# amplifier.net
KiCad netlist of a schematic drawn in EAGLE
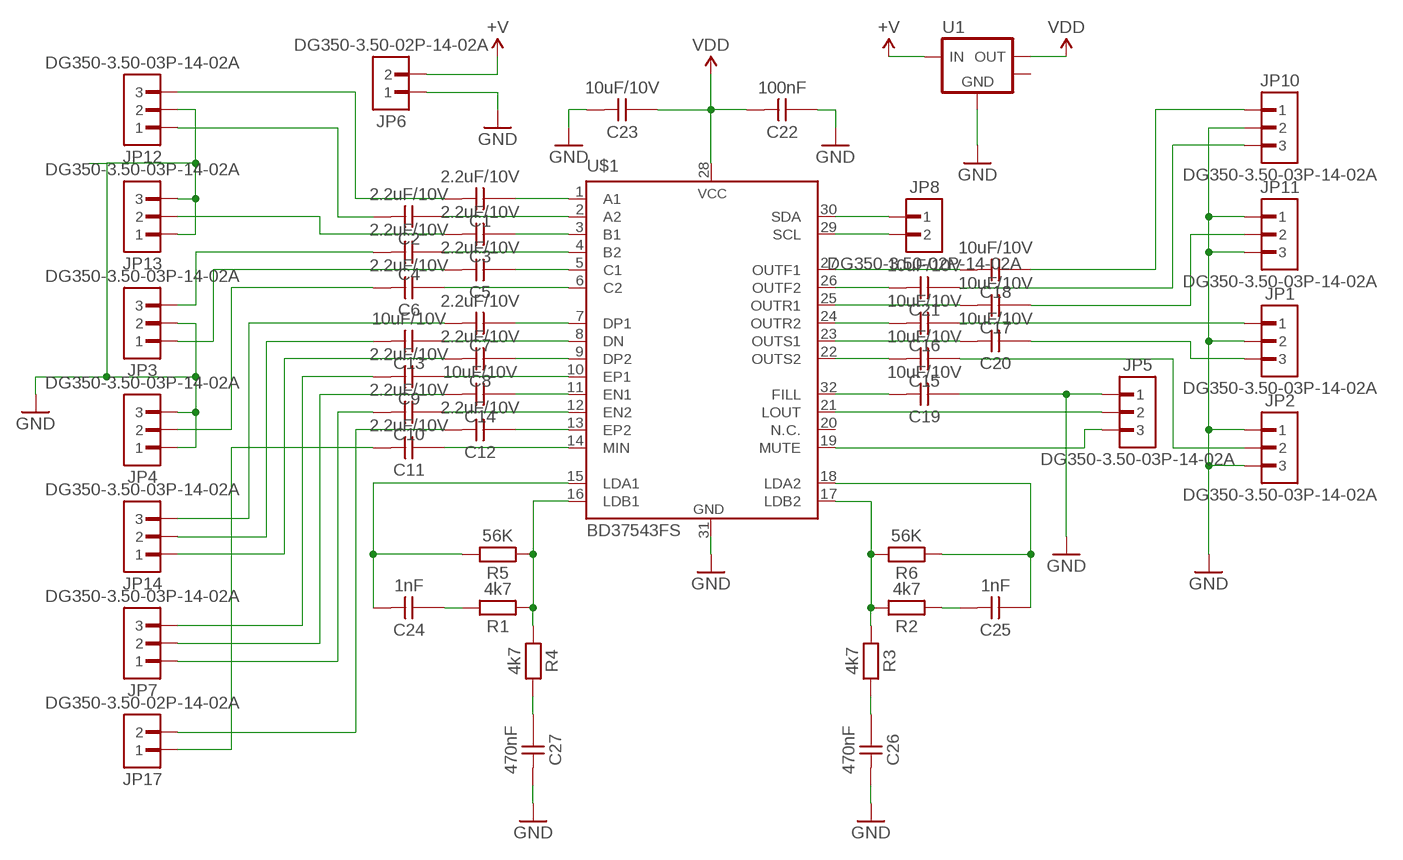
[diagram p0: schematic, sheet 1]

(export (version "E")
  (design (tool "Eeschema 10.0.6"))
  (components
    (comp (ref "C1")
      (value "2.2uF/10V")
      (footprint "eagle-import:CAPACITOR-0805_R")
      (libsource (lib "eagle-import") (part "C-0805-2.2UF-10V"))
    )
    (comp (ref "C2")
      (value "2.2uF/10V")
      (footprint "eagle-import:CAPACITOR-0805_R")
      (libsource (lib "eagle-import") (part "C-0805-2.2UF-10V"))
    )
    (comp (ref "C3")
      (value "2.2uF/10V")
      (footprint "eagle-import:CAPACITOR-0805_R")
      (libsource (lib "eagle-import") (part "C-0805-2.2UF-10V"))
    )
    (comp (ref "C4")
      (value "2.2uF/10V")
      (footprint "eagle-import:CAPACITOR-0805_R")
      (libsource (lib "eagle-import") (part "C-0805-2.2UF-10V"))
    )
    (comp (ref "C5")
      (value "2.2uF/10V")
      (footprint "eagle-import:CAPACITOR-0805_R")
      (libsource (lib "eagle-import") (part "C-0805-2.2UF-10V"))
    )
    (comp (ref "C6")
      (value "2.2uF/10V")
      (footprint "eagle-import:CAPACITOR-0805_R")
      (libsource (lib "eagle-import") (part "C-0805-2.2UF-10V"))
    )
    (comp (ref "C7")
      (value "2.2uF/10V")
      (footprint "eagle-import:CAPACITOR-0805_R")
      (libsource (lib "eagle-import") (part "C-0805-2.2UF-10V"))
    )
    (comp (ref "C8")
      (value "2.2uF/10V")
      (footprint "eagle-import:CAPACITOR-0805_R")
      (libsource (lib "eagle-import") (part "C-0805-2.2UF-10V"))
    )
    (comp (ref "C9")
      (value "2.2uF/10V")
      (footprint "eagle-import:CAPACITOR-0805_R")
      (libsource (lib "eagle-import") (part "C-0805-2.2UF-10V"))
    )
    (comp (ref "C10")
      (value "2.2uF/10V")
      (footprint "eagle-import:CAPACITOR-0805_R")
      (libsource (lib "eagle-import") (part "C-0805-2.2UF-10V"))
    )
    (comp (ref "C11")
      (value "2.2uF/10V")
      (footprint "eagle-import:CAPACITOR-0805_R")
      (libsource (lib "eagle-import") (part "C-0805-2.2UF-10V"))
    )
    (comp (ref "C12")
      (value "2.2uF/10V")
      (footprint "eagle-import:CAPACITOR-0805_R")
      (libsource (lib "eagle-import") (part "C-0805-2.2UF-10V"))
    )
    (comp (ref "C13")
      (value "10uF/10V")
      (footprint "eagle-import:CAPACITOR-0805_R")
      (libsource (lib "eagle-import") (part "C-0805-10UF-10V"))
    )
    (comp (ref "C14")
      (value "10uF/10V")
      (footprint "eagle-import:CAPACITOR-0805_R")
      (libsource (lib "eagle-import") (part "C-0805-10UF-10V"))
    )
    (comp (ref "C15")
      (value "10uF/10V")
      (footprint "eagle-import:CAPACITOR-0805_R")
      (libsource (lib "eagle-import") (part "C-0805-10UF-10V"))
    )
    (comp (ref "C16")
      (value "10uF/10V")
      (footprint "eagle-import:CAPACITOR-0805_R")
      (libsource (lib "eagle-import") (part "C-0805-10UF-10V"))
    )
    (comp (ref "C17")
      (value "10uF/10V")
      (footprint "eagle-import:CAPACITOR-0805_R")
      (libsource (lib "eagle-import") (part "C-0805-10UF-10V"))
    )
    (comp (ref "C18")
      (value "10uF/10V")
      (footprint "eagle-import:CAPACITOR-0805_R")
      (libsource (lib "eagle-import") (part "C-0805-10UF-10V"))
    )
    (comp (ref "C19")
      (value "10uF/10V")
      (footprint "eagle-import:CAPACITOR-0805_R")
      (libsource (lib "eagle-import") (part "C-0805-10UF-10V"))
    )
    (comp (ref "C20")
      (value "10uF/10V")
      (footprint "eagle-import:CAPACITOR-0805_R")
      (libsource (lib "eagle-import") (part "C-0805-10UF-10V"))
    )
    (comp (ref "C21")
      (value "10uF/10V")
      (footprint "eagle-import:CAPACITOR-0805_R")
      (libsource (lib "eagle-import") (part "C-0805-10UF-10V"))
    )
    (comp (ref "C22")
      (value "100nF")
      (footprint "eagle-import:CAPACITOR-0805_R")
      (libsource (lib "eagle-import") (part "C-0805-100NF"))
    )
    (comp (ref "C23")
      (value "10uF/10V")
      (footprint "eagle-import:CAPACITOR-0805_R")
      (libsource (lib "eagle-import") (part "C-0805-10UF-10V"))
    )
    (comp (ref "C24")
      (value "1nF")
      (footprint "eagle-import:CAPACITOR-0805_R")
      (libsource (lib "eagle-import") (part "C-0805-1NF"))
    )
    (comp (ref "C25")
      (value "1nF")
      (footprint "eagle-import:CAPACITOR-0805_R")
      (libsource (lib "eagle-import") (part "C-0805-1NF"))
    )
    (comp (ref "C26")
      (value "470nF")
      (footprint "eagle-import:CAPACITOR-0805_R")
      (libsource (lib "eagle-import") (part "C-0805-470NF"))
    )
    (comp (ref "C27")
      (value "470nF")
      (footprint "eagle-import:CAPACITOR-0805_R")
      (libsource (lib "eagle-import") (part "C-0805-470NF"))
    )
    (comp (ref "JP1")
      (value "DG350-3.50-03P-14-02A")
      (footprint "eagle-import:DG350-3.50-03P-14-02A_T")
      (libsource (lib "eagle-import") (part "JP-DG350-3.50-03P-14-02A"))
    )
    (comp (ref "JP2")
      (value "DG350-3.50-03P-14-02A")
      (footprint "eagle-import:DG350-3.50-03P-14-02A_T")
      (libsource (lib "eagle-import") (part "JP-DG350-3.50-03P-14-02A"))
    )
    (comp (ref "JP3")
      (value "DG350-3.50-03P-14-02A")
      (footprint "eagle-import:DG350-3.50-03P-14-02A_T")
      (libsource (lib "eagle-import") (part "JP-DG350-3.50-03P-14-02A"))
    )
    (comp (ref "JP4")
      (value "DG350-3.50-03P-14-02A")
      (footprint "eagle-import:DG350-3.50-03P-14-02A_T")
      (libsource (lib "eagle-import") (part "JP-DG350-3.50-03P-14-02A"))
    )
    (comp (ref "JP5")
      (value "DG350-3.50-03P-14-02A")
      (footprint "eagle-import:DG350-3.50-03P-14-02A_T")
      (libsource (lib "eagle-import") (part "JP-DG350-3.50-03P-14-02A"))
    )
    (comp (ref "JP6")
      (value "DG350-3.50-02P-14-02A")
      (footprint "eagle-import:DG350-3.50-02P-14-02A_T")
      (libsource (lib "eagle-import") (part "JP-DG350-3.50-02P-14-02A"))
    )
    (comp (ref "JP7")
      (value "DG350-3.50-03P-14-02A")
      (footprint "eagle-import:DG350-3.50-03P-14-02A_T")
      (libsource (lib "eagle-import") (part "JP-DG350-3.50-03P-14-02A"))
    )
    (comp (ref "JP8")
      (value "DG350-3.50-02P-14-02A")
      (footprint "eagle-import:DG350-3.50-02P-14-02A_T")
      (libsource (lib "eagle-import") (part "JP-DG350-3.50-02P-14-02A"))
    )
    (comp (ref "JP10")
      (value "DG350-3.50-03P-14-02A")
      (footprint "eagle-import:DG350-3.50-03P-14-02A_T")
      (libsource (lib "eagle-import") (part "JP-DG350-3.50-03P-14-02A"))
    )
    (comp (ref "JP11")
      (value "DG350-3.50-03P-14-02A")
      (footprint "eagle-import:DG350-3.50-03P-14-02A_T")
      (libsource (lib "eagle-import") (part "JP-DG350-3.50-03P-14-02A"))
    )
    (comp (ref "JP12")
      (value "DG350-3.50-03P-14-02A")
      (footprint "eagle-import:DG350-3.50-03P-14-02A_T")
      (libsource (lib "eagle-import") (part "JP-DG350-3.50-03P-14-02A"))
    )
    (comp (ref "JP13")
      (value "DG350-3.50-03P-14-02A")
      (footprint "eagle-import:DG350-3.50-03P-14-02A_T")
      (libsource (lib "eagle-import") (part "JP-DG350-3.50-03P-14-02A"))
    )
    (comp (ref "JP14")
      (value "DG350-3.50-03P-14-02A")
      (footprint "eagle-import:DG350-3.50-03P-14-02A_T")
      (libsource (lib "eagle-import") (part "JP-DG350-3.50-03P-14-02A"))
    )
    (comp (ref "JP17")
      (value "DG350-3.50-02P-14-02A")
      (footprint "eagle-import:DG350-3.50-02P-14-02A_T")
      (libsource (lib "eagle-import") (part "JP-DG350-3.50-02P-14-02A"))
    )
    (comp (ref "R1")
      (value "4k7")
      (footprint "eagle-import:RESISTOR-0805_R")
      (libsource (lib "eagle-import") (part "R-0805-4K7"))
    )
    (comp (ref "R2")
      (value "4k7")
      (footprint "eagle-import:RESISTOR-0805_R")
      (libsource (lib "eagle-import") (part "R-0805-4K7"))
    )
    (comp (ref "R3")
      (value "4k7")
      (footprint "eagle-import:RESISTOR-0805_R")
      (libsource (lib "eagle-import") (part "R-0805-4K7"))
    )
    (comp (ref "R4")
      (value "4k7")
      (footprint "eagle-import:RESISTOR-0805_R")
      (libsource (lib "eagle-import") (part "R-0805-4K7"))
    )
    (comp (ref "R5")
      (value "56K")
      (footprint "eagle-import:RESISTOR-0805_R")
      (libsource (lib "eagle-import") (part "R-0805"))
    )
    (comp (ref "R6")
      (value "56K")
      (footprint "eagle-import:RESISTOR-0805_R")
      (libsource (lib "eagle-import") (part "R-0805"))
    )
    (comp (ref "U$1")
      (value "BD37543FS")
      (footprint "eagle-import:SSOP32")
      (libsource (lib "eagle-import") (part "BD37543FS"))
    )
    (comp (ref "U1")
      (value "LM2940KTT")
      (footprint "eagle-import:TO263-3")
      (libsource (lib "eagle-import") (part "LM2940KTT"))
    )
  )
  (nets
    (net (code "1") (name "+V") (class "Default")
      (node (ref "JP6") (pin "2") (pinfunction "2_2") (pintype "passive"))
      (node (ref "U1") (pin "1") (pinfunction "VIN_1") (pintype "power_in"))
    )
    (net (code "2") (name "/TAB") (class "Default")
      (node (ref "U1") (pin "TAB") (pinfunction "TAB_TAB") (pintype "power_in"))
    )
    (net (code "3") (name "GND") (class "Default")
      (node (ref "C19") (pin "2") (pinfunction "2_2") (pintype "passive"))
      (node (ref "C22") (pin "2") (pinfunction "2_2") (pintype "passive"))
      (node (ref "C23") (pin "1") (pinfunction "1_1") (pintype "passive"))
      (node (ref "C26") (pin "1") (pinfunction "1_1") (pintype "passive"))
      (node (ref "C27") (pin "1") (pinfunction "1_1") (pintype "passive"))
      (node (ref "JP1") (pin "2") (pinfunction "2_2") (pintype "passive"))
      (node (ref "JP10") (pin "2") (pinfunction "2_2") (pintype "passive"))
      (node (ref "JP11") (pin "1") (pinfunction "1_1") (pintype "passive"))
      (node (ref "JP11") (pin "3") (pinfunction "3_3") (pintype "passive"))
      (node (ref "JP12") (pin "2") (pinfunction "2_2") (pintype "passive"))
      (node (ref "JP13") (pin "1") (pinfunction "1_1") (pintype "passive"))
      (node (ref "JP13") (pin "3") (pinfunction "3_3") (pintype "passive"))
      (node (ref "JP2") (pin "1") (pinfunction "1_1") (pintype "passive"))
      (node (ref "JP2") (pin "3") (pinfunction "3_3") (pintype "passive"))
      (node (ref "JP3") (pin "2") (pinfunction "2_2") (pintype "passive"))
      (node (ref "JP4") (pin "1") (pinfunction "1_1") (pintype "passive"))
      (node (ref "JP4") (pin "3") (pinfunction "3_3") (pintype "passive"))
      (node (ref "JP5") (pin "1") (pinfunction "1_1") (pintype "passive"))
      (node (ref "JP6") (pin "1") (pinfunction "1_1") (pintype "passive"))
      (node (ref "U$1") (pin "31") (pinfunction "GND_31") (pintype "power_in"))
      (node (ref "U1") (pin "2") (pinfunction "GND_2") (pintype "power_in"))
    )
    (net (code "4") (name "Net-(C1-Pad1)") (class "Default")
      (node (ref "C1") (pin "1") (pinfunction "1_1") (pintype "passive"))
      (node (ref "JP12") (pin "3") (pinfunction "3_3") (pintype "passive"))
    )
    (net (code "5") (name "Net-(C2-Pad1)") (class "Default")
      (node (ref "C2") (pin "1") (pinfunction "1_1") (pintype "passive"))
      (node (ref "JP12") (pin "1") (pinfunction "1_1") (pintype "passive"))
    )
    (net (code "6") (name "Net-(C3-Pad1)") (class "Default")
      (node (ref "C3") (pin "1") (pinfunction "1_1") (pintype "passive"))
      (node (ref "JP13") (pin "2") (pinfunction "2_2") (pintype "passive"))
    )
    (net (code "7") (name "Net-(C4-Pad1)") (class "Default")
      (node (ref "C4") (pin "1") (pinfunction "1_1") (pintype "passive"))
      (node (ref "JP3") (pin "3") (pinfunction "3_3") (pintype "passive"))
    )
    (net (code "8") (name "Net-(C5-Pad1)") (class "Default")
      (node (ref "C5") (pin "1") (pinfunction "1_1") (pintype "passive"))
      (node (ref "JP3") (pin "1") (pinfunction "1_1") (pintype "passive"))
    )
    (net (code "9") (name "Net-(C6-Pad1)") (class "Default")
      (node (ref "C6") (pin "1") (pinfunction "1_1") (pintype "passive"))
      (node (ref "JP4") (pin "2") (pinfunction "2_2") (pintype "passive"))
    )
    (net (code "10") (name "Net-(C7-Pad1)") (class "Default")
      (node (ref "C7") (pin "1") (pinfunction "1_1") (pintype "passive"))
      (node (ref "JP14") (pin "3") (pinfunction "3_3") (pintype "passive"))
    )
    (net (code "11") (name "Net-(C8-Pad1)") (class "Default")
      (node (ref "C8") (pin "1") (pinfunction "1_1") (pintype "passive"))
      (node (ref "JP14") (pin "1") (pinfunction "1_1") (pintype "passive"))
    )
    (net (code "12") (name "Net-(C9-Pad1)") (class "Default")
      (node (ref "C9") (pin "1") (pinfunction "1_1") (pintype "passive"))
      (node (ref "JP7") (pin "3") (pinfunction "3_3") (pintype "passive"))
    )
    (net (code "13") (name "Net-(C10-Pad1)") (class "Default")
      (node (ref "C10") (pin "1") (pinfunction "1_1") (pintype "passive"))
      (node (ref "JP7") (pin "1") (pinfunction "1_1") (pintype "passive"))
    )
    (net (code "14") (name "Net-(C11-Pad1)") (class "Default")
      (node (ref "C11") (pin "1") (pinfunction "1_1") (pintype "passive"))
      (node (ref "JP17") (pin "1") (pinfunction "1_1") (pintype "passive"))
    )
    (net (code "15") (name "Net-(C12-Pad1)") (class "Default")
      (node (ref "C12") (pin "1") (pinfunction "1_1") (pintype "passive"))
      (node (ref "JP17") (pin "2") (pinfunction "2_2") (pintype "passive"))
    )
    (net (code "16") (name "Net-(C13-Pad1)") (class "Default")
      (node (ref "C13") (pin "1") (pinfunction "1_1") (pintype "passive"))
      (node (ref "JP14") (pin "2") (pinfunction "2_2") (pintype "passive"))
    )
    (net (code "17") (name "Net-(C14-Pad1)") (class "Default")
      (node (ref "C14") (pin "1") (pinfunction "1_1") (pintype "passive"))
      (node (ref "JP7") (pin "2") (pinfunction "2_2") (pintype "passive"))
    )
    (net (code "18") (name "Net-(C15-Pad2)") (class "Default")
      (node (ref "C15") (pin "2") (pinfunction "2_2") (pintype "passive"))
      (node (ref "JP2") (pin "2") (pinfunction "2_2") (pintype "passive"))
    )
    (net (code "19") (name "Net-(C16-Pad2)") (class "Default")
      (node (ref "C16") (pin "2") (pinfunction "2_2") (pintype "passive"))
      (node (ref "JP1") (pin "1") (pinfunction "1_1") (pintype "passive"))
    )
    (net (code "20") (name "Net-(C17-Pad2)") (class "Default")
      (node (ref "C17") (pin "2") (pinfunction "2_2") (pintype "passive"))
      (node (ref "JP11") (pin "2") (pinfunction "2_2") (pintype "passive"))
    )
    (net (code "21") (name "Net-(C18-Pad2)") (class "Default")
      (node (ref "C18") (pin "2") (pinfunction "2_2") (pintype "passive"))
      (node (ref "JP10") (pin "1") (pinfunction "1_1") (pintype "passive"))
    )
    (net (code "22") (name "Net-(C20-Pad2)") (class "Default")
      (node (ref "C20") (pin "2") (pinfunction "2_2") (pintype "passive"))
      (node (ref "JP1") (pin "3") (pinfunction "3_3") (pintype "passive"))
    )
    (net (code "23") (name "Net-(C21-Pad2)") (class "Default")
      (node (ref "C21") (pin "2") (pinfunction "2_2") (pintype "passive"))
      (node (ref "JP10") (pin "3") (pinfunction "3_3") (pintype "passive"))
    )
    (net (code "24") (name "Net-(C24-Pad2)") (class "Default")
      (node (ref "C24") (pin "2") (pinfunction "2_2") (pintype "passive"))
      (node (ref "R1") (pin "2") (pinfunction "2_2") (pintype "passive"))
    )
    (net (code "25") (name "Net-(C25-Pad1)") (class "Default")
      (node (ref "C25") (pin "1") (pinfunction "1_1") (pintype "passive"))
      (node (ref "R2") (pin "1") (pinfunction "1_1") (pintype "passive"))
    )
    (net (code "26") (name "Net-(C26-Pad2)") (class "Default")
      (node (ref "C26") (pin "2") (pinfunction "2_2") (pintype "passive"))
      (node (ref "R3") (pin "2") (pinfunction "2_2") (pintype "passive"))
    )
    (net (code "27") (name "Net-(C27-Pad2)") (class "Default")
      (node (ref "C27") (pin "2") (pinfunction "2_2") (pintype "passive"))
      (node (ref "R4") (pin "2") (pinfunction "2_2") (pintype "passive"))
    )
    (net (code "28") (name "Net-(U$1-A1)") (class "Default")
      (node (ref "C1") (pin "2") (pinfunction "2_2") (pintype "passive"))
      (node (ref "U$1") (pin "1") (pinfunction "A1_1") (pintype "input"))
    )
    (net (code "29") (name "Net-(U$1-A2)") (class "Default")
      (node (ref "C2") (pin "2") (pinfunction "2_2") (pintype "passive"))
      (node (ref "U$1") (pin "2") (pinfunction "A2_2") (pintype "bidirectional"))
    )
    (net (code "30") (name "Net-(U$1-B1)") (class "Default")
      (node (ref "C3") (pin "2") (pinfunction "2_2") (pintype "passive"))
      (node (ref "U$1") (pin "3") (pinfunction "B1_3") (pintype "bidirectional"))
    )
    (net (code "31") (name "Net-(U$1-B2)") (class "Default")
      (node (ref "C4") (pin "2") (pinfunction "2_2") (pintype "passive"))
      (node (ref "U$1") (pin "4") (pinfunction "B2_4") (pintype "bidirectional"))
    )
    (net (code "32") (name "Net-(U$1-C1)") (class "Default")
      (node (ref "C5") (pin "2") (pinfunction "2_2") (pintype "passive"))
      (node (ref "U$1") (pin "5") (pinfunction "C1_5") (pintype "bidirectional"))
    )
    (net (code "33") (name "Net-(U$1-C2)") (class "Default")
      (node (ref "C6") (pin "2") (pinfunction "2_2") (pintype "passive"))
      (node (ref "U$1") (pin "6") (pinfunction "C2_6") (pintype "bidirectional"))
    )
    (net (code "34") (name "Net-(U$1-DN)") (class "Default")
      (node (ref "C13") (pin "2") (pinfunction "2_2") (pintype "passive"))
      (node (ref "U$1") (pin "8") (pinfunction "DN_8") (pintype "bidirectional"))
    )
    (net (code "35") (name "Net-(U$1-DP1)") (class "Default")
      (node (ref "C7") (pin "2") (pinfunction "2_2") (pintype "passive"))
      (node (ref "U$1") (pin "7") (pinfunction "DP1_7") (pintype "bidirectional"))
    )
    (net (code "36") (name "Net-(U$1-DP2)") (class "Default")
      (node (ref "C8") (pin "2") (pinfunction "2_2") (pintype "passive"))
      (node (ref "U$1") (pin "9") (pinfunction "DP2_9") (pintype "bidirectional"))
    )
    (net (code "37") (name "Net-(U$1-EN1)") (class "Default")
      (node (ref "C14") (pin "2") (pinfunction "2_2") (pintype "passive"))
      (node (ref "U$1") (pin "11") (pinfunction "EN1_11") (pintype "bidirectional"))
    )
    (net (code "38") (name "Net-(U$1-EN2)") (class "Default")
      (node (ref "C10") (pin "2") (pinfunction "2_2") (pintype "passive"))
      (node (ref "U$1") (pin "12") (pinfunction "EN2_12") (pintype "bidirectional"))
    )
    (net (code "39") (name "Net-(U$1-EP1)") (class "Default")
      (node (ref "C9") (pin "2") (pinfunction "2_2") (pintype "passive"))
      (node (ref "U$1") (pin "10") (pinfunction "EP1_10") (pintype "bidirectional"))
    )
    (net (code "40") (name "Net-(U$1-EP2)") (class "Default")
      (node (ref "C12") (pin "2") (pinfunction "2_2") (pintype "passive"))
      (node (ref "U$1") (pin "13") (pinfunction "EP2_13") (pintype "bidirectional"))
    )
    (net (code "41") (name "Net-(U$1-FILL)") (class "Default")
      (node (ref "C19") (pin "1") (pinfunction "1_1") (pintype "passive"))
      (node (ref "U$1") (pin "32") (pinfunction "FILL_32") (pintype "bidirectional"))
    )
    (net (code "42") (name "Net-(U$1-LDA1)") (class "Default")
      (node (ref "C24") (pin "1") (pinfunction "1_1") (pintype "passive"))
      (node (ref "R5") (pin "2") (pinfunction "2_2") (pintype "passive"))
      (node (ref "U$1") (pin "15") (pinfunction "LDA1_15") (pintype "bidirectional"))
    )
    (net (code "43") (name "Net-(U$1-LDA2)") (class "Default")
      (node (ref "C25") (pin "2") (pinfunction "2_2") (pintype "passive"))
      (node (ref "R6") (pin "1") (pinfunction "1_1") (pintype "passive"))
      (node (ref "U$1") (pin "18") (pinfunction "LDA2_18") (pintype "bidirectional"))
    )
    (net (code "44") (name "Net-(U$1-LDB1)") (class "Default")
      (node (ref "R1") (pin "1") (pinfunction "1_1") (pintype "passive"))
      (node (ref "R4") (pin "1") (pinfunction "1_1") (pintype "passive"))
      (node (ref "R5") (pin "1") (pinfunction "1_1") (pintype "passive"))
      (node (ref "U$1") (pin "16") (pinfunction "LDB1_16") (pintype "bidirectional"))
    )
    (net (code "45") (name "Net-(U$1-LDB2)") (class "Default")
      (node (ref "R2") (pin "2") (pinfunction "2_2") (pintype "passive"))
      (node (ref "R3") (pin "1") (pinfunction "1_1") (pintype "passive"))
      (node (ref "R6") (pin "2") (pinfunction "2_2") (pintype "passive"))
      (node (ref "U$1") (pin "17") (pinfunction "LDB2_17") (pintype "bidirectional"))
    )
    (net (code "46") (name "Net-(U$1-LOUT)") (class "Default")
      (node (ref "JP5") (pin "2") (pinfunction "2_2") (pintype "passive"))
      (node (ref "U$1") (pin "21") (pinfunction "LOUT_21") (pintype "bidirectional"))
    )
    (net (code "47") (name "Net-(U$1-MIN)") (class "Default")
      (node (ref "C11") (pin "2") (pinfunction "2_2") (pintype "passive"))
      (node (ref "U$1") (pin "14") (pinfunction "MIN_14") (pintype "bidirectional"))
    )
    (net (code "48") (name "Net-(U$1-MUTE)") (class "Default")
      (node (ref "JP5") (pin "3") (pinfunction "3_3") (pintype "passive"))
      (node (ref "U$1") (pin "19") (pinfunction "MUTE_19") (pintype "bidirectional"))
    )
    (net (code "49") (name "Net-(U$1-OUTF1)") (class "Default")
      (node (ref "C18") (pin "1") (pinfunction "1_1") (pintype "passive"))
      (node (ref "U$1") (pin "27") (pinfunction "OUTF1_27") (pintype "bidirectional"))
    )
    (net (code "50") (name "Net-(U$1-OUTF2)") (class "Default")
      (node (ref "C21") (pin "1") (pinfunction "1_1") (pintype "passive"))
      (node (ref "U$1") (pin "26") (pinfunction "OUTF2_26") (pintype "bidirectional"))
    )
    (net (code "51") (name "Net-(U$1-OUTR1)") (class "Default")
      (node (ref "C17") (pin "1") (pinfunction "1_1") (pintype "passive"))
      (node (ref "U$1") (pin "25") (pinfunction "OUTR1_25") (pintype "bidirectional"))
    )
    (net (code "52") (name "Net-(U$1-OUTR2)") (class "Default")
      (node (ref "C16") (pin "1") (pinfunction "1_1") (pintype "passive"))
      (node (ref "U$1") (pin "24") (pinfunction "OUTR2_24") (pintype "bidirectional"))
    )
    (net (code "53") (name "Net-(U$1-OUTS1)") (class "Default")
      (node (ref "C20") (pin "1") (pinfunction "1_1") (pintype "passive"))
      (node (ref "U$1") (pin "23") (pinfunction "OUTS1_23") (pintype "bidirectional"))
    )
    (net (code "54") (name "Net-(U$1-OUTS2)") (class "Default")
      (node (ref "C15") (pin "1") (pinfunction "1_1") (pintype "passive"))
      (node (ref "U$1") (pin "22") (pinfunction "OUTS2_22") (pintype "bidirectional"))
    )
    (net (code "55") (name "Net-(U$1-SCL)") (class "Default")
      (node (ref "JP8") (pin "2") (pinfunction "2_2") (pintype "passive"))
      (node (ref "U$1") (pin "29") (pinfunction "SCL_29") (pintype "bidirectional"))
    )
    (net (code "56") (name "Net-(U$1-SDA)") (class "Default")
      (node (ref "JP8") (pin "1") (pinfunction "1_1") (pintype "passive"))
      (node (ref "U$1") (pin "30") (pinfunction "SDA_30") (pintype "bidirectional"))
    )
    (net (code "57") (name "VDD") (class "Default")
      (node (ref "C22") (pin "1") (pinfunction "1_1") (pintype "passive"))
      (node (ref "C23") (pin "2") (pinfunction "2_2") (pintype "passive"))
      (node (ref "U$1") (pin "28") (pinfunction "VCC_28") (pintype "power_in"))
      (node (ref "U1") (pin "3") (pinfunction "VOUT_3") (pintype "power_in"))
    )
    (net (code "58") (name "unconnected-(U$1-N.C.-Pad20)") (class "Default")
      (node (ref "U$1") (pin "20") (pinfunction "N.C._20") (pintype "bidirectional"))
    )
  )
)
